# Example_Board.net
KiCad netlist of a schematic drawn in Altium Designer
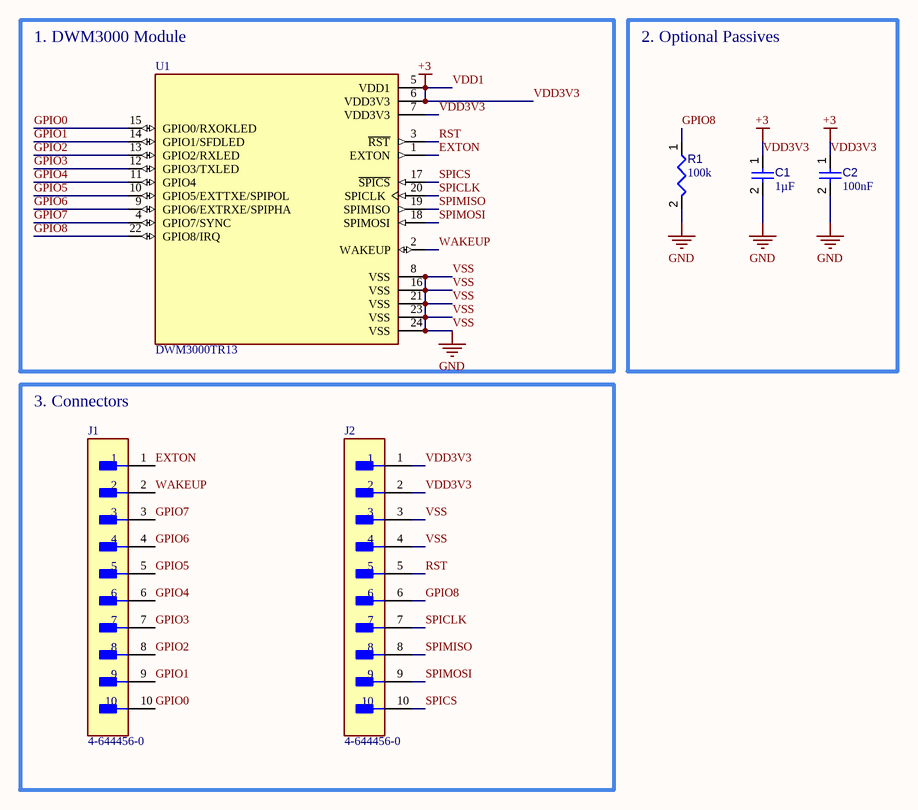
[diagram p0: Example Board.SchDoc]

(export (version "E")
  (design (tool "Eeschema 10.0.6"))
  (components
    (comp (ref "C1")
      (value "1µF")
      (footprint "CAPC0402(1005)60_L")
      (description "Chip Capacitor, 1µF +/-20%, 10V, 0402, Thickness 0.6 mm")
      (fields (field (name "TOLERANCE") "10%") (field (name "Comment") "Capacitor 1µF +/-20% 10V 0402"))
      (libsource (lib "SUBC") (part "CAP-NP-2"))
    )
    (comp (ref "C2")
      (value "100nF")
      (footprint "CAPC0402(1005)60_L")
      (description "Chip Capacitor, 100nF +/-20%, 25V, 0402, Thickness 0.6 mm")
      (fields (field (name "TOLERANCE") "10%") (field (name "Comment") "Capacitor 100nF +/-20% 25V 0402"))
      (libsource (lib "SUBC") (part "CAP-NP-2"))
    )
    (comp (ref "J1")
      (value "4-644456-0")
      (footprint "FP-4-644456-0-MFG")
      (description "Conn Unshrouded Header HDR 10 POS 2.54mm Solder ST Top Entry Thru-Hole Bag/Box")
      (libsource (lib "SUBC") (part "aee40dc8b284c03a16094555aa210be"))
    )
    (comp (ref "J2")
      (value "4-644456-0")
      (footprint "FP-4-644456-0-MFG")
      (description "Conn Unshrouded Header HDR 10 POS 2.54mm Solder ST Top Entry Thru-Hole Bag/Box")
      (libsource (lib "SUBC") (part "aee40dc8b284c03a16094555aa210be"))
    )
    (comp (ref "R1")
      (value "100k")
      (footprint "RESC1608X55X25ML10T15")
      (description "Chip Resistor, 100 KOhm, +/- 1%, 0.1 W, -55 to 155 degC, 0603 (1608 Metric)")
      (fields (field (name "TOLERANCE") "1%") (field (name "POWER") "100mW"))
      (libsource (lib "SUBC") (part "RES-2"))
    )
    (comp (ref "U1")
      (value "DWM3000TR13")
      (footprint "XCVR_DWM3000TR13")
      (description "RF Modules DW1000 based module")
      (fields (field (name "MF") "Qorvo"))
      (libsource (lib "SUBC") (part "DWM3000TR13"))
    )
  )
  (nets
    (net (code "1") (name "+3") (class "Default")
      (node (ref "C1") (pin "1") (pinfunction "1_1") (pintype "passive"))
      (node (ref "C2") (pin "1") (pinfunction "1_1") (pintype "passive"))
      (node (ref "J2") (pin "1") (pinfunction "1_1") (pintype "passive"))
      (node (ref "J2") (pin "2") (pinfunction "2_2") (pintype "passive"))
      (node (ref "U1") (pin "5") (pinfunction "VDD1_5") (pintype "power_in"))
      (node (ref "U1") (pin "6") (pinfunction "VDD3V3_6") (pintype "power_in"))
      (node (ref "U1") (pin "7") (pinfunction "VDD3V3_7") (pintype "power_in"))
    )
    (net (code "2") (name "/EXTON") (class "Default")
      (node (ref "J1") (pin "1") (pinfunction "1_1") (pintype "passive"))
      (node (ref "U1") (pin "1") (pinfunction "EXTON_1") (pintype "output"))
    )
    (net (code "3") (name "/GPIO0") (class "Default")
      (node (ref "J1") (pin "10") (pinfunction "10_10") (pintype "passive"))
      (node (ref "U1") (pin "15") (pinfunction "GPIO0/RXOKLED_15") (pintype "bidirectional"))
    )
    (net (code "4") (name "/GPIO1") (class "Default")
      (node (ref "J1") (pin "9") (pinfunction "9_9") (pintype "passive"))
      (node (ref "U1") (pin "14") (pinfunction "GPIO1/SFDLED_14") (pintype "bidirectional"))
    )
    (net (code "5") (name "/GPIO2") (class "Default")
      (node (ref "J1") (pin "8") (pinfunction "8_8") (pintype "passive"))
      (node (ref "U1") (pin "13") (pinfunction "GPIO2/RXLED_13") (pintype "bidirectional"))
    )
    (net (code "6") (name "/GPIO3") (class "Default")
      (node (ref "J1") (pin "7") (pinfunction "7_7") (pintype "passive"))
      (node (ref "U1") (pin "12") (pinfunction "GPIO3/TXLED_12") (pintype "bidirectional"))
    )
    (net (code "7") (name "/GPIO4") (class "Default")
      (node (ref "J1") (pin "6") (pinfunction "6_6") (pintype "passive"))
      (node (ref "U1") (pin "11") (pinfunction "GPIO4_11") (pintype "bidirectional"))
    )
    (net (code "8") (name "/GPIO5") (class "Default")
      (node (ref "J1") (pin "5") (pinfunction "5_5") (pintype "passive"))
      (node (ref "U1") (pin "10") (pinfunction "GPIO5/EXTTXE/SPIPOL_10") (pintype "bidirectional"))
    )
    (net (code "9") (name "/GPIO6") (class "Default")
      (node (ref "J1") (pin "4") (pinfunction "4_4") (pintype "passive"))
      (node (ref "U1") (pin "9") (pinfunction "GPIO6/EXTRXE/SPIPHA_9") (pintype "bidirectional"))
    )
    (net (code "10") (name "/GPIO7") (class "Default")
      (node (ref "J1") (pin "3") (pinfunction "3_3") (pintype "passive"))
      (node (ref "U1") (pin "4") (pinfunction "GPIO7/SYNC_4") (pintype "bidirectional"))
    )
    (net (code "11") (name "/GPIO8") (class "Default")
      (node (ref "J2") (pin "6") (pinfunction "6_6") (pintype "passive"))
      (node (ref "R1") (pin "1") (pinfunction "1_1") (pintype "passive"))
      (node (ref "U1") (pin "22") (pinfunction "GPIO8/IRQ_22") (pintype "bidirectional"))
    )
    (net (code "12") (name "/RST") (class "Default")
      (node (ref "J2") (pin "5") (pinfunction "5_5") (pintype "passive"))
      (node (ref "U1") (pin "3") (pinfunction "~{RST}_3") (pintype "output"))
    )
    (net (code "13") (name "/SPICLK") (class "Default")
      (node (ref "J2") (pin "7") (pinfunction "7_7") (pintype "passive"))
      (node (ref "U1") (pin "20") (pinfunction "SPICLK_20") (pintype "input"))
    )
    (net (code "14") (name "/SPICS") (class "Default")
      (node (ref "J2") (pin "10") (pinfunction "10_10") (pintype "passive"))
      (node (ref "U1") (pin "17") (pinfunction "~{SPICS}_17") (pintype "input"))
    )
    (net (code "15") (name "/SPIMISO") (class "Default")
      (node (ref "J2") (pin "8") (pinfunction "8_8") (pintype "passive"))
      (node (ref "U1") (pin "19") (pinfunction "SPIMISO_19") (pintype "output"))
    )
    (net (code "16") (name "/SPIMOSI") (class "Default")
      (node (ref "J2") (pin "9") (pinfunction "9_9") (pintype "passive"))
      (node (ref "U1") (pin "18") (pinfunction "SPIMOSI_18") (pintype "input"))
    )
    (net (code "17") (name "/WAKEUP") (class "Default")
      (node (ref "J1") (pin "2") (pinfunction "2_2") (pintype "passive"))
      (node (ref "U1") (pin "2") (pinfunction "WAKEUP_2") (pintype "bidirectional"))
    )
    (net (code "18") (name "GND") (class "Default")
      (node (ref "C1") (pin "2") (pinfunction "2_2") (pintype "passive"))
      (node (ref "C2") (pin "2") (pinfunction "2_2") (pintype "passive"))
      (node (ref "J2") (pin "3") (pinfunction "3_3") (pintype "passive"))
      (node (ref "J2") (pin "4") (pinfunction "4_4") (pintype "passive"))
      (node (ref "R1") (pin "2") (pinfunction "2_2") (pintype "passive"))
      (node (ref "U1") (pin "16") (pinfunction "VSS_16") (pintype "power_in"))
      (node (ref "U1") (pin "21") (pinfunction "VSS_21") (pintype "power_in"))
      (node (ref "U1") (pin "23") (pinfunction "VSS_23") (pintype "power_in"))
      (node (ref "U1") (pin "24") (pinfunction "VSS_24") (pintype "power_in"))
      (node (ref "U1") (pin "8") (pinfunction "VSS_8") (pintype "power_in"))
    )
  )
)
